# Soil_Sensor_Board.net
KiCad netlist of a schematic drawn in EAGLE
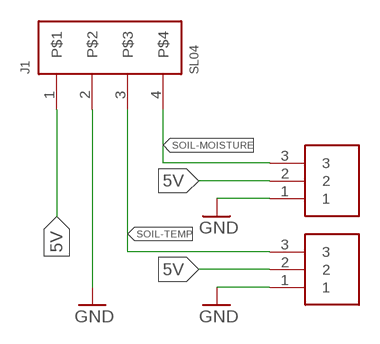
[diagram p0: schematic, sheet 1]

(export (version "E")
  (design (tool "Eeschema 10.0.6"))
  (components
    (comp (ref "J1")
      (value "SL04")
      (footprint "eagle-import:MOLEX_SL_04_TH")
      (libsource (lib "eagle-import") (part "SL04"))
    )
    (comp (ref "J2")
      (value "SL03THROUGH_HOLE")
      (footprint "eagle-import:MOLEX_SL_03_TH")
      (fields (field (name "PARTNO") "0705550002"))
      (libsource (lib "eagle-import") (part "SL03THROUGH_HOLE"))
    )
    (comp (ref "J3")
      (value "SL03THROUGH_HOLE")
      (footprint "eagle-import:MOLEX_SL_03_TH")
      (fields (field (name "PARTNO") "0705550002"))
      (libsource (lib "eagle-import") (part "SL03THROUGH_HOLE"))
    )
  )
  (nets
    (net (code "1") (name "5V") (class "Default")
      (node (ref "J1") (pin "1") (pinfunction "P$1_1") (pintype "bidirectional"))
      (node (ref "J2") (pin "2") (pinfunction "2_2") (pintype "bidirectional"))
      (node (ref "J3") (pin "2") (pinfunction "2_2") (pintype "bidirectional"))
    )
    (net (code "2") (name "GND") (class "Default")
      (node (ref "J1") (pin "2") (pinfunction "P$2_2") (pintype "bidirectional"))
      (node (ref "J2") (pin "1") (pinfunction "1_1") (pintype "bidirectional"))
      (node (ref "J3") (pin "1") (pinfunction "1_1") (pintype "bidirectional"))
    )
    (net (code "3") (name "SOIL-MOISTURE") (class "Default")
      (node (ref "J1") (pin "4") (pinfunction "P$4_4") (pintype "bidirectional"))
      (node (ref "J2") (pin "3") (pinfunction "3_3") (pintype "bidirectional"))
    )
    (net (code "4") (name "SOIL-TEMP") (class "Default")
      (node (ref "J1") (pin "3") (pinfunction "P$3_3") (pintype "bidirectional"))
      (node (ref "J3") (pin "3") (pinfunction "3_3") (pintype "bidirectional"))
    )
  )
)
